# rf_antenna.net
KiCad netlist of a schematic drawn in Altium Designer
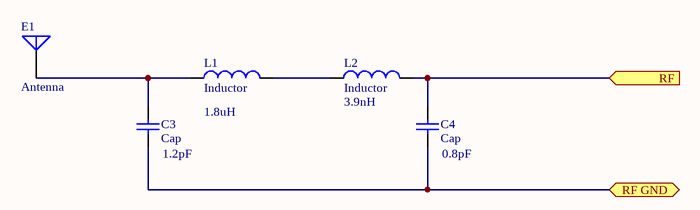
[diagram p0: rf_antenna.SchDoc]

(export (version "E")
  (design (tool "Eeschema 10.0.6"))
  (components
    (comp (ref "C3")
      (value "Cap")
      (footprint "RAD-0.3")
      (description "Capacitor")
      (fields (field (name "ALTIUM_VALUE") "1.2pF") (field (name "PUBLISHER") "Altium Limited"))
      (libsource (lib "Miscellaneous Devices") (part "Cap"))
    )
    (comp (ref "C4")
      (value "Cap")
      (footprint "RAD-0.3")
      (description "Capacitor")
      (fields (field (name "ALTIUM_VALUE") "0.8pF") (field (name "PUBLISHER") "Altium Limited"))
      (libsource (lib "Miscellaneous Devices") (part "Cap"))
    )
    (comp (ref "E1")
      (value "Antenna")
      (footprint "PIN1")
      (description "Generic Antenna")
      (fields (field (name "PUBLISHER") "Altium Limited"))
      (libsource (lib "Miscellaneous Devices") (part "Antenna"))
    )
    (comp (ref "L1")
      (value "Inductor")
      (footprint "0402-A")
      (fields (field (name "ALTIUM_VALUE") "1.8uH") (field (name "PUBLISHER") "Altium Limited"))
      (libsource (lib "Miscellaneous Devices") (part "Inductor"))
    )
    (comp (ref "L2")
      (value "Inductor")
      (footprint "0402-A")
      (fields (field (name "ALTIUM_VALUE") "3.9nH") (field (name "PUBLISHER") "Altium Limited"))
      (libsource (lib "Miscellaneous Devices") (part "Inductor"))
    )
  )
  (nets
    (net (code "1") (name "/RF") (class "Default")
      (node (ref "C4") (pin "1") (pinfunction "1_1") (pintype "passive"))
      (node (ref "L2") (pin "2") (pinfunction "2_2") (pintype "passive"))
    )
    (net (code "2") (name "/RF GND") (class "Default")
      (node (ref "C3") (pin "2") (pinfunction "2_2") (pintype "passive"))
      (node (ref "C4") (pin "2") (pinfunction "2_2") (pintype "passive"))
    )
    (net (code "3") (name "Net-(E1-A)") (class "Default")
      (node (ref "C3") (pin "1") (pinfunction "1_1") (pintype "passive"))
      (node (ref "E1") (pin "1") (pinfunction "A_1") (pintype "passive"))
      (node (ref "L1") (pin "1") (pinfunction "1_1") (pintype "passive"))
    )
    (net (code "4") (name "Net-(L1-Pad2)") (class "Default")
      (node (ref "L1") (pin "2") (pinfunction "2_2") (pintype "passive"))
      (node (ref "L2") (pin "1") (pinfunction "1_1") (pintype "passive"))
    )
  )
)
